# 009pcb5.net
KiCad netlist of a schematic drawn in EAGLE
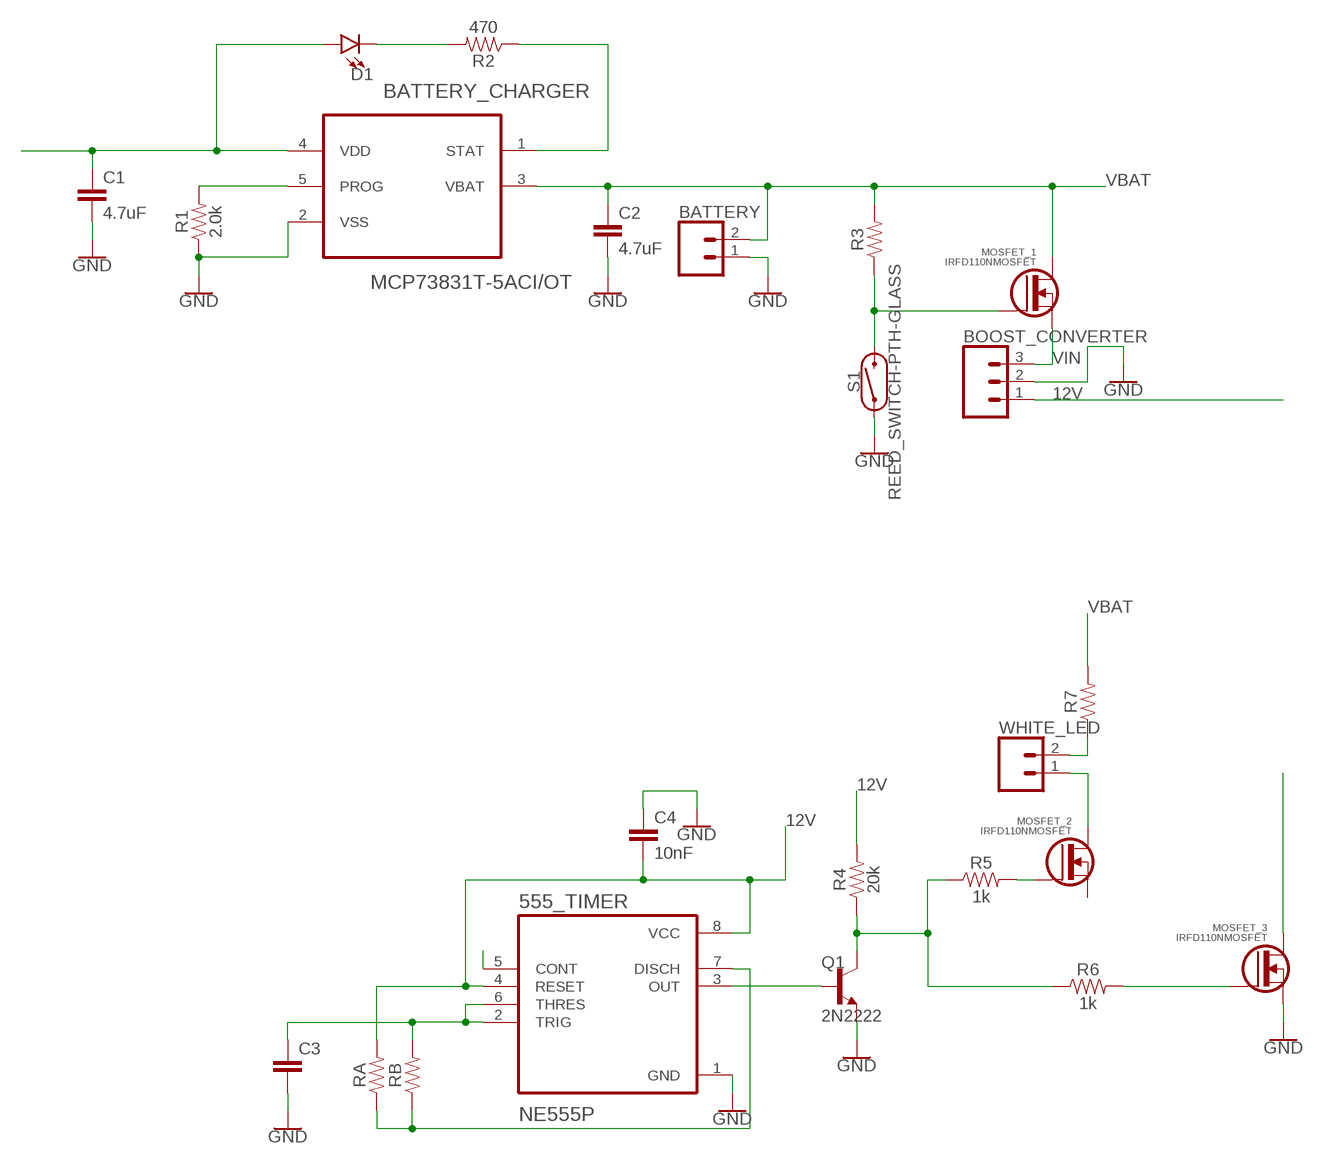
[diagram p0: schematic, sheet 1]

(export (version "E")
  (design (tool "Eeschema 10.0.6"))
  (components
    (comp (ref "555_TIMER")
      (value "NE555P")
      (footprint "eagle-import:DIP794W45P254L959H508Q8")
      (fields (field (name "DIGI-KEY_PART_NUMBER") "296-NE555P-ND") (field (name "MF") "Texas"))
      (libsource (lib "eagle-import") (part "NE555P"))
    )
    (comp (ref "BATTERY")
      (value "CONN_02")
      (footprint "eagle-import:1X02")
      (libsource (lib "eagle-import") (part "CONN_02"))
    )
    (comp (ref "BATTERY_CHARGER")
      (value "MCP73831T-5ACI/OT")
      (footprint "eagle-import:SOT95P280X145-5N")
      (fields
        (field (name "DIGI-KEY_PART_NUMBER") "MCP73831T-5ACI/OTTR-ND")
        (field (name "MF") "Microchip Technology")
      )
      (libsource (lib "eagle-import") (part "MCP73831T-5ACI/OT"))
    )
    (comp (ref "BOOST_CONVERTER")
      (value "CONN_03")
      (footprint "eagle-import:1X03")
      (libsource (lib "eagle-import") (part "CONN_03"))
    )
    (comp (ref "C1")
      (value "4.7uF")
      (footprint "eagle-import:1206")
      (libsource (lib "eagle-import") (part "4.7UF-1206-16V-(+80/-20%)"))
    )
    (comp (ref "C2")
      (value "4.7uF")
      (footprint "eagle-import:1206")
      (libsource (lib "eagle-import") (part "4.7UF-1206-16V-(+80/-20%)"))
    )
    (comp (ref "C3")
      (value "4.7UF-1206-16V-(+80/-20%)")
      (footprint "eagle-import:1206")
      (libsource (lib "eagle-import") (part "4.7UF-1206-16V-(+80/-20%)"))
    )
    (comp (ref "C4")
      (value "10nF")
      (footprint "eagle-import:0603")
      (libsource (lib "eagle-import") (part "10NF-0603-50V-10%"))
    )
    (comp (ref "D1")
      (value "LED5MM")
      (footprint "eagle-import:LED_5MM")
      (libsource (lib "eagle-import") (part "LED5MM"))
    )
    (comp (ref "MOSFET_1")
      (value "IRFD110NMOSFET")
      (footprint "eagle-import:DIP4")
      (fields (field (name "MF") "Vishay Siliconix") (field (name "MP") "IRFD110"))
      (libsource (lib "eagle-import") (part "IRFD110NMOSFET"))
    )
    (comp (ref "MOSFET_2")
      (value "IRFD110NMOSFET")
      (footprint "eagle-import:DIP4")
      (fields (field (name "MF") "Vishay Siliconix") (field (name "MP") "IRFD110"))
      (libsource (lib "eagle-import") (part "IRFD110NMOSFET"))
    )
    (comp (ref "MOSFET_3")
      (value "IRFD110NMOSFET")
      (footprint "eagle-import:DIP4")
      (fields (field (name "MF") "Vishay Siliconix") (field (name "MP") "IRFD110"))
      (libsource (lib "eagle-import") (part "IRFD110NMOSFET"))
    )
    (comp (ref "Q1")
      (value "2N2222")
      (footprint "eagle-import:TO127P580H530-3")
      (fields (field (name "MF") "STMicroelectronics"))
      (libsource (lib "eagle-import") (part "2N2222"))
    )
    (comp (ref "R1")
      (value "2.0k")
      (footprint "eagle-import:0603")
      (libsource (lib "eagle-import") (part "2.0KOHM-0603-1/10W-5%"))
    )
    (comp (ref "R2")
      (value "470")
      (footprint "eagle-import:0603")
      (libsource (lib "eagle-import") (part "470OHM-0603-1/10W-1%"))
    )
    (comp (ref "R3")
      (value "1OHM-0603-1/10W-1%")
      (footprint "eagle-import:0603")
      (libsource (lib "eagle-import") (part "1OHM-0603-1/10W-1%"))
    )
    (comp (ref "R4")
      (value "20k")
      (footprint "eagle-import:0603")
      (libsource (lib "eagle-import") (part "20KOHM-0603-1/10W-1%"))
    )
    (comp (ref "R5")
      (value "1k")
      (footprint "eagle-import:0603")
      (libsource (lib "eagle-import") (part "1KOHM-0603-1/10W-1%"))
    )
    (comp (ref "R6")
      (value "1k")
      (footprint "eagle-import:0603")
      (libsource (lib "eagle-import") (part "1KOHM-0603-1/10W-1%"))
    )
    (comp (ref "R7")
      (value "1OHM-0603-1/10W-1%")
      (footprint "eagle-import:0603")
      (libsource (lib "eagle-import") (part "1OHM-0603-1/10W-1%"))
    )
    (comp (ref "RA")
      (value "1OHM-0603-1/10W-1%")
      (footprint "eagle-import:0603")
      (libsource (lib "eagle-import") (part "1OHM-0603-1/10W-1%"))
    )
    (comp (ref "RB")
      (value "1OHM-0603-1/10W-1%")
      (footprint "eagle-import:0603")
      (libsource (lib "eagle-import") (part "1OHM-0603-1/10W-1%"))
    )
    (comp (ref "S1")
      (value "REED_SWITCH-PTH-GLASS")
      (footprint "eagle-import:REED_SWITCH_GLASS")
      (libsource (lib "eagle-import") (part "REED_SWITCH-PTH-GLASS"))
    )
    (comp (ref "WHITE_LED")
      (value "CONN_02")
      (footprint "eagle-import:1X02")
      (libsource (lib "eagle-import") (part "CONN_02"))
    )
  )
  (nets
    (net (code "1") (name "/12V") (class "Default")
      (node (ref "555_TIMER") (pin "4") (pinfunction "RESET_4") (pintype "input"))
      (node (ref "555_TIMER") (pin "8") (pinfunction "VCC_8") (pintype "power_in"))
      (node (ref "BOOST_CONVERTER") (pin "1") (pinfunction "1_1") (pintype "passive"))
      (node (ref "C4") (pin "2") (pinfunction "2_2") (pintype "passive"))
      (node (ref "R4") (pin "2") (pinfunction "2_2") (pintype "passive"))
      (node (ref "RA") (pin "2") (pinfunction "2_2") (pintype "passive"))
    )
    (net (code "2") (name "/VBAT") (class "Default")
      (node (ref "BATTERY") (pin "2") (pinfunction "2_2") (pintype "passive"))
      (node (ref "BATTERY_CHARGER") (pin "3") (pinfunction "VBAT_3") (pintype "output"))
      (node (ref "C2") (pin "1") (pinfunction "1_1") (pintype "passive"))
      (node (ref "MOSFET_1") (pin "D") (pinfunction "D_D") (pintype "passive"))
      (node (ref "R3") (pin "2") (pinfunction "2_2") (pintype "passive"))
      (node (ref "R7") (pin "2") (pinfunction "2_2") (pintype "passive"))
    )
    (net (code "3") (name "/VIN") (class "Default")
      (node (ref "BOOST_CONVERTER") (pin "3") (pinfunction "3_3") (pintype "passive"))
      (node (ref "MOSFET_1") (pin "S") (pinfunction "S_S") (pintype "passive"))
    )
    (net (code "4") (name "GND") (class "Default")
      (node (ref "555_TIMER") (pin "1") (pinfunction "GND_1") (pintype "power_in"))
      (node (ref "BATTERY") (pin "1") (pinfunction "1_1") (pintype "passive"))
      (node (ref "BATTERY_CHARGER") (pin "2") (pinfunction "VSS_2") (pintype "power_in"))
      (node (ref "BOOST_CONVERTER") (pin "2") (pinfunction "2_2") (pintype "passive"))
      (node (ref "C1") (pin "2") (pinfunction "2_2") (pintype "passive"))
      (node (ref "C2") (pin "2") (pinfunction "2_2") (pintype "passive"))
      (node (ref "C3") (pin "2") (pinfunction "2_2") (pintype "passive"))
      (node (ref "C4") (pin "1") (pinfunction "1_1") (pintype "passive"))
      (node (ref "MOSFET_3") (pin "S") (pinfunction "S_S") (pintype "passive"))
      (node (ref "Q1") (pin "1") (pinfunction "E_1") (pintype "passive"))
      (node (ref "R1") (pin "1") (pinfunction "1_1") (pintype "passive"))
      (node (ref "S1") (pin "P$1") (pinfunction "1_P$1") (pintype "passive"))
    )
    (net (code "5") (name "Net-(555_TIMER-DISCH)") (class "Default")
      (node (ref "555_TIMER") (pin "7") (pinfunction "DISCH_7") (pintype "output"))
      (node (ref "RA") (pin "1") (pinfunction "1_1") (pintype "passive"))
      (node (ref "RB") (pin "1") (pinfunction "1_1") (pintype "passive"))
    )
    (net (code "6") (name "Net-(555_TIMER-OUT)") (class "Default")
      (node (ref "555_TIMER") (pin "3") (pinfunction "OUT_3") (pintype "output"))
      (node (ref "Q1") (pin "2") (pinfunction "B_2") (pintype "passive"))
    )
    (net (code "7") (name "Net-(555_TIMER-THRES)") (class "Default")
      (node (ref "555_TIMER") (pin "2") (pinfunction "TRIG_2") (pintype "input"))
      (node (ref "555_TIMER") (pin "6") (pinfunction "THRES_6") (pintype "input"))
      (node (ref "C3") (pin "1") (pinfunction "1_1") (pintype "passive"))
      (node (ref "RB") (pin "2") (pinfunction "2_2") (pintype "passive"))
    )
    (net (code "8") (name "Net-(BATTERY_CHARGER-PROG)") (class "Default")
      (node (ref "BATTERY_CHARGER") (pin "5") (pinfunction "PROG_5") (pintype "input"))
      (node (ref "R1") (pin "2") (pinfunction "2_2") (pintype "passive"))
    )
    (net (code "9") (name "Net-(BATTERY_CHARGER-STAT)") (class "Default")
      (node (ref "BATTERY_CHARGER") (pin "1") (pinfunction "STAT_1") (pintype "output"))
      (node (ref "R2") (pin "1") (pinfunction "1_1") (pintype "passive"))
    )
    (net (code "10") (name "Net-(BATTERY_CHARGER-VDD)") (class "Default")
      (node (ref "BATTERY_CHARGER") (pin "4") (pinfunction "VDD_4") (pintype "power_in"))
      (node (ref "C1") (pin "1") (pinfunction "1_1") (pintype "passive"))
      (node (ref "D1") (pin "A") (pinfunction "A_A") (pintype "passive"))
    )
    (net (code "11") (name "Net-(D1-C)") (class "Default")
      (node (ref "D1") (pin "K") (pinfunction "C_K") (pintype "passive"))
      (node (ref "R2") (pin "2") (pinfunction "2_2") (pintype "passive"))
    )
    (net (code "12") (name "Net-(MOSFET_2-PadD)") (class "Default")
      (node (ref "MOSFET_2") (pin "D") (pinfunction "D_D") (pintype "passive"))
      (node (ref "WHITE_LED") (pin "1") (pinfunction "1_1") (pintype "passive"))
    )
    (net (code "13") (name "Net-(MOSFET_2-PadG)") (class "Default")
      (node (ref "MOSFET_2") (pin "G") (pinfunction "G_G") (pintype "passive"))
      (node (ref "R5") (pin "2") (pinfunction "2_2") (pintype "passive"))
    )
    (net (code "14") (name "Net-(MOSFET_3-PadG)") (class "Default")
      (node (ref "MOSFET_3") (pin "G") (pinfunction "G_G") (pintype "passive"))
      (node (ref "R6") (pin "2") (pinfunction "2_2") (pintype "passive"))
    )
    (net (code "15") (name "Net-(Q1-C)") (class "Default")
      (node (ref "Q1") (pin "3") (pinfunction "C_3") (pintype "passive"))
      (node (ref "R4") (pin "1") (pinfunction "1_1") (pintype "passive"))
      (node (ref "R5") (pin "1") (pinfunction "1_1") (pintype "passive"))
      (node (ref "R6") (pin "1") (pinfunction "1_1") (pintype "passive"))
    )
    (net (code "16") (name "Net-(R7-Pad1)") (class "Default")
      (node (ref "R7") (pin "1") (pinfunction "1_1") (pintype "passive"))
      (node (ref "WHITE_LED") (pin "2") (pinfunction "2_2") (pintype "passive"))
    )
    (net (code "17") (name "Net-(S1-2)") (class "Default")
      (node (ref "MOSFET_1") (pin "G") (pinfunction "G_G") (pintype "passive"))
      (node (ref "R3") (pin "1") (pinfunction "1_1") (pintype "passive"))
      (node (ref "S1") (pin "P$2") (pinfunction "2_P$2") (pintype "passive"))
    )
    (net (code "18") (name "unconnected-(555_TIMER-CONT-Pad5)") (class "Default")
      (node (ref "555_TIMER") (pin "5") (pinfunction "CONT_5") (pintype "input"))
    )
    (net (code "19") (name "unconnected-(MOSFET_1-PadD1)") (class "Default")
      (node (ref "MOSFET_1") (pin "D1") (pinfunction "D1_D1") (pintype "bidirectional"))
    )
    (net (code "20") (name "unconnected-(MOSFET_2-PadD1)") (class "Default")
      (node (ref "MOSFET_2") (pin "D1") (pinfunction "D1_D1") (pintype "bidirectional"))
    )
    (net (code "21") (name "unconnected-(MOSFET_2-PadS)") (class "Default")
      (node (ref "MOSFET_2") (pin "S") (pinfunction "S_S") (pintype "passive"))
    )
    (net (code "22") (name "unconnected-(MOSFET_3-PadD)") (class "Default")
      (node (ref "MOSFET_3") (pin "D") (pinfunction "D_D") (pintype "passive"))
    )
    (net (code "23") (name "unconnected-(MOSFET_3-PadD1)") (class "Default")
      (node (ref "MOSFET_3") (pin "D1") (pinfunction "D1_D1") (pintype "bidirectional"))
    )
  )
)
